# Main.net
KiCad netlist of a schematic drawn in Altium Designer
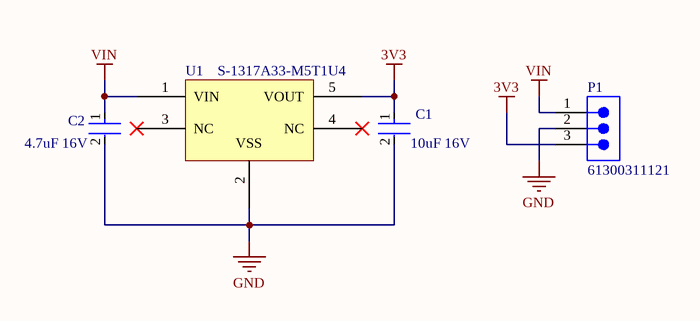
[diagram p0: Main.SchDoc]

(export (version "E")
  (design (tool "Eeschema 10.0.6"))
  (components
    (comp (ref "C1")
      (value "10uF 16V")
      (footprint "FP-CC0603-DC-MFG")
      (description "CM105X5R106K16AT")
      (fields (field (name "TOLERANCE") "10%"))
      (libsource (lib "Altium Content Vault") (part "b4654b650e69147ec39a6b967a45e02"))
    )
    (comp (ref "C2")
      (value "4.7uF 16V")
      (footprint "FP-CC0603-DA-MFG")
      (description "GRM188Z71C475KE21D")
      (fields
        (field (name "MANUFACTURER") "YAGEO")
        (field (name "MANUFACTURER PART NUMBER") "CC0603KRX5R7BB475")
      )
      (libsource (lib "Altium Content Vault") (part "11868f565c42a9108669ba33697ecf6"))
    )
    (comp (ref "P1")
      (value "61300311121")
      (footprint "61300311121")
      (description "THT Vertical Pin Header WR-PHD, Pitch 2.54 mm, Single Row, 3 pins")
      (libsource (lib "Altium Content Vault") (part "Header_Male_1R_03P"))
    )
    (comp (ref "U1")
      (value "S-1317A33-M5T1U4")
      (footprint "S-1317A33-M5T1U4")
      (libsource (lib "1317A33-M5T1U4") (part "S-1317A33-M5T1U4"))
    )
  )
  (nets
    (net (code "1") (name "3V3") (class "Default")
      (node (ref "C1") (pin "1") (pinfunction "1_1") (pintype "passive"))
      (node (ref "P1") (pin "3") (pinfunction "3_3") (pintype "passive"))
      (node (ref "U1") (pin "5") (pinfunction "VOUT_5") (pintype "passive"))
    )
    (net (code "2") (name "GND") (class "Default")
      (node (ref "C1") (pin "2") (pinfunction "2_2") (pintype "passive"))
      (node (ref "C2") (pin "2") (pinfunction "2_2") (pintype "passive"))
      (node (ref "P1") (pin "2") (pinfunction "2_2") (pintype "passive"))
      (node (ref "U1") (pin "2") (pinfunction "VSS_2") (pintype "passive"))
    )
    (net (code "3") (name "VIN") (class "Default")
      (node (ref "C2") (pin "1") (pinfunction "1_1") (pintype "passive"))
      (node (ref "P1") (pin "1") (pinfunction "1_1") (pintype "passive"))
      (node (ref "U1") (pin "1") (pinfunction "VIN_1") (pintype "passive"))
    )
    (net (code "4") (name "unconnected-(U1-NC-Pad3)") (class "Default")
      (node (ref "U1") (pin "3") (pinfunction "NC_3") (pintype "passive+no_connect"))
    )
    (net (code "5") (name "unconnected-(U1-NC-Pad4)") (class "Default")
      (node (ref "U1") (pin "4") (pinfunction "NC_4") (pintype "passive+no_connect"))
    )
  )
)
